# main_new.net
KiCad netlist of a schematic drawn in EAGLE
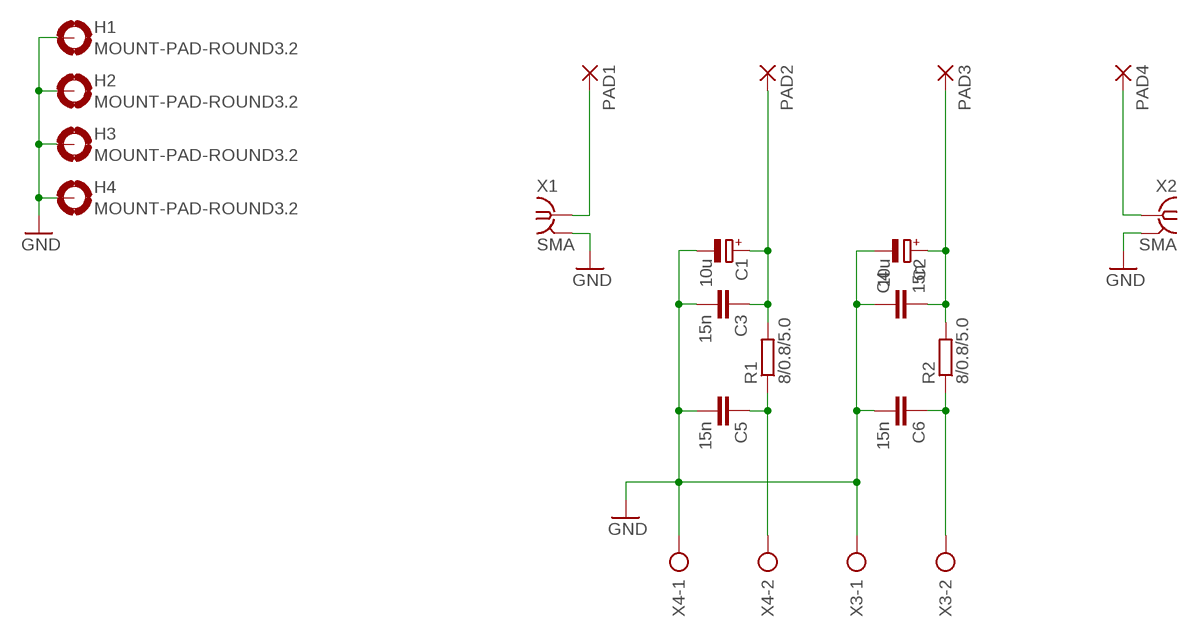
[diagram p0: schematic, sheet 1]

(export (version "E")
  (design (tool "Eeschema 10.0.6"))
  (components
    (comp (ref "C1")
      (value "10u")
      (footprint "eagle-import:E5-8,5")
      (libsource (lib "eagle-import") (part "CPOL-EUE5-8.5"))
    )
    (comp (ref "C2")
      (value "10u")
      (footprint "eagle-import:E5-8,5")
      (libsource (lib "eagle-import") (part "CPOL-EUE5-8.5"))
    )
    (comp (ref "C3")
      (value "15n")
      (footprint "eagle-import:C050-030X075")
      (libsource (lib "eagle-import") (part "C-EU050-030X075"))
    )
    (comp (ref "C4")
      (value "15n")
      (footprint "eagle-import:C050-030X075")
      (libsource (lib "eagle-import") (part "C-EU050-030X075"))
    )
    (comp (ref "C5")
      (value "15n")
      (footprint "eagle-import:C050-030X075")
      (libsource (lib "eagle-import") (part "C-EU050-030X075"))
    )
    (comp (ref "C6")
      (value "15n")
      (footprint "eagle-import:C050-030X075")
      (libsource (lib "eagle-import") (part "C-EU050-030X075"))
    )
    (comp (ref "H1")
      (value "MOUNT-PAD-ROUND3.2")
      (footprint "eagle-import:3,2-PAD")
      (libsource (lib "eagle-import") (part "MOUNT-PAD-ROUND3.2"))
    )
    (comp (ref "H2")
      (value "MOUNT-PAD-ROUND3.2")
      (footprint "eagle-import:3,2-PAD")
      (libsource (lib "eagle-import") (part "MOUNT-PAD-ROUND3.2"))
    )
    (comp (ref "H3")
      (value "MOUNT-PAD-ROUND3.2")
      (footprint "eagle-import:3,2-PAD")
      (libsource (lib "eagle-import") (part "MOUNT-PAD-ROUND3.2"))
    )
    (comp (ref "H4")
      (value "MOUNT-PAD-ROUND3.2")
      (footprint "eagle-import:3,2-PAD")
      (libsource (lib "eagle-import") (part "MOUNT-PAD-ROUND3.2"))
    )
    (comp (ref "PAD1")
      (value "SMD5")
      (footprint "eagle-import:SMD2,54-5,08")
      (libsource (lib "eagle-import") (part "SMD5"))
    )
    (comp (ref "PAD2")
      (value "SMD5")
      (footprint "eagle-import:SMD2,54-5,08")
      (libsource (lib "eagle-import") (part "SMD5"))
    )
    (comp (ref "PAD3")
      (value "SMD5")
      (footprint "eagle-import:SMD2,54-5,08")
      (libsource (lib "eagle-import") (part "SMD5"))
    )
    (comp (ref "PAD4")
      (value "SMD5")
      (footprint "eagle-import:SMD2,54-5,08")
      (libsource (lib "eagle-import") (part "SMD5"))
    )
    (comp (ref "R1")
      (value "8/0.8/5.0")
      (footprint "eagle-import:0411_12")
      (libsource (lib "eagle-import") (part "R-EU_0411/12"))
    )
    (comp (ref "R2")
      (value "8/0.8/5.0")
      (footprint "eagle-import:0411_12")
      (libsource (lib "eagle-import") (part "R-EU_0411/12"))
    )
    (comp (ref "X1")
      (value "SMA")
      (footprint "eagle-import:J502-ND-142-0711-821_826")
      (fields (field (name "MF") "JOHNSON COMPONENTS") (field (name "MPN") "142-0711-821"))
      (libsource (lib "eagle-import") (part "SMA-142-0711-821/826"))
    )
    (comp (ref "X2")
      (value "SMA")
      (footprint "eagle-import:J502-ND-142-0711-821_826")
      (fields (field (name "MF") "JOHNSON COMPONENTS") (field (name "MPN") "142-0711-821"))
      (libsource (lib "eagle-import") (part "SMA-142-0711-821/826"))
    )
    (comp (ref "X3")
      (value "AK500/2")
      (footprint "eagle-import:AK500_2")
      (libsource (lib "eagle-import") (part "AK500/2"))
    )
    (comp (ref "X4")
      (value "AK500/2")
      (footprint "eagle-import:AK500_2")
      (libsource (lib "eagle-import") (part "AK500/2"))
    )
  )
  (nets
    (net (code "1") (name "GND") (class "Default")
      (node (ref "C1") (pin "-") (pinfunction "-_-") (pintype "passive"))
      (node (ref "C2") (pin "-") (pinfunction "-_-") (pintype "passive"))
      (node (ref "C3") (pin "2") (pinfunction "2_2") (pintype "passive"))
      (node (ref "C4") (pin "1") (pinfunction "1_1") (pintype "passive"))
      (node (ref "C5") (pin "2") (pinfunction "2_2") (pintype "passive"))
      (node (ref "C6") (pin "2") (pinfunction "2_2") (pintype "passive"))
      (node (ref "H1") (pin "B3,2") (pinfunction "MOUNT_B3,2") (pintype "passive"))
      (node (ref "H2") (pin "B3,2") (pinfunction "MOUNT_B3,2") (pintype "passive"))
      (node (ref "H3") (pin "B3,2") (pinfunction "MOUNT_B3,2") (pintype "passive"))
      (node (ref "H4") (pin "B3,2") (pinfunction "MOUNT_B3,2") (pintype "passive"))
      (node (ref "X1") (pin "G@1") (pinfunction "2_G@1") (pintype "passive"))
      (node (ref "X1") (pin "G@2") (pinfunction "2_G@2") (pintype "passive"))
      (node (ref "X1") (pin "G@3") (pinfunction "2_G@3") (pintype "passive"))
      (node (ref "X1") (pin "G@4") (pinfunction "2_G@4") (pintype "passive"))
      (node (ref "X2") (pin "G@1") (pinfunction "2_G@1") (pintype "passive"))
      (node (ref "X2") (pin "G@2") (pinfunction "2_G@2") (pintype "passive"))
      (node (ref "X2") (pin "G@3") (pinfunction "2_G@3") (pintype "passive"))
      (node (ref "X2") (pin "G@4") (pinfunction "2_G@4") (pintype "passive"))
      (node (ref "X3") (pin "1") (pinfunction "KL_1") (pintype "passive"))
      (node (ref "X4") (pin "1") (pinfunction "KL_1") (pintype "passive"))
    )
    (net (code "2") (name "Net-(PAD1-P)") (class "Default")
      (node (ref "PAD1") (pin "1") (pinfunction "P_1") (pintype "passive"))
      (node (ref "X1") (pin "1") (pinfunction "1_1") (pintype "passive"))
    )
    (net (code "3") (name "Net-(PAD2-P)") (class "Default")
      (node (ref "C1") (pin "+") (pinfunction "+_+") (pintype "passive"))
      (node (ref "C3") (pin "1") (pinfunction "1_1") (pintype "passive"))
      (node (ref "PAD2") (pin "1") (pinfunction "P_1") (pintype "passive"))
      (node (ref "R1") (pin "2") (pinfunction "2_2") (pintype "passive"))
    )
    (net (code "4") (name "Net-(PAD3-P)") (class "Default")
      (node (ref "C2") (pin "+") (pinfunction "+_+") (pintype "passive"))
      (node (ref "C4") (pin "2") (pinfunction "2_2") (pintype "passive"))
      (node (ref "PAD3") (pin "1") (pinfunction "P_1") (pintype "passive"))
      (node (ref "R2") (pin "2") (pinfunction "2_2") (pintype "passive"))
    )
    (net (code "5") (name "Net-(PAD4-P)") (class "Default")
      (node (ref "PAD4") (pin "1") (pinfunction "P_1") (pintype "passive"))
      (node (ref "X2") (pin "1") (pinfunction "1_1") (pintype "passive"))
    )
    (net (code "6") (name "Net-(X3B-KL)") (class "Default")
      (node (ref "C6") (pin "1") (pinfunction "1_1") (pintype "passive"))
      (node (ref "R2") (pin "1") (pinfunction "1_1") (pintype "passive"))
      (node (ref "X3") (pin "2") (pinfunction "KL_2") (pintype "passive"))
    )
    (net (code "7") (name "Net-(X4B-KL)") (class "Default")
      (node (ref "C5") (pin "1") (pinfunction "1_1") (pintype "passive"))
      (node (ref "R1") (pin "1") (pinfunction "1_1") (pintype "passive"))
      (node (ref "X4") (pin "2") (pinfunction "KL_2") (pintype "passive"))
    )
  )
)
